# temp_module_v2_0_nov2023.net
KiCad netlist of a schematic drawn in EAGLE
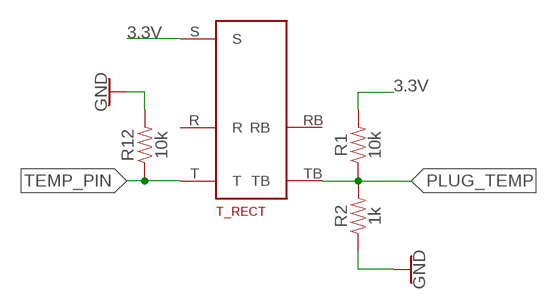
[diagram p0: schematic, sheet 1]
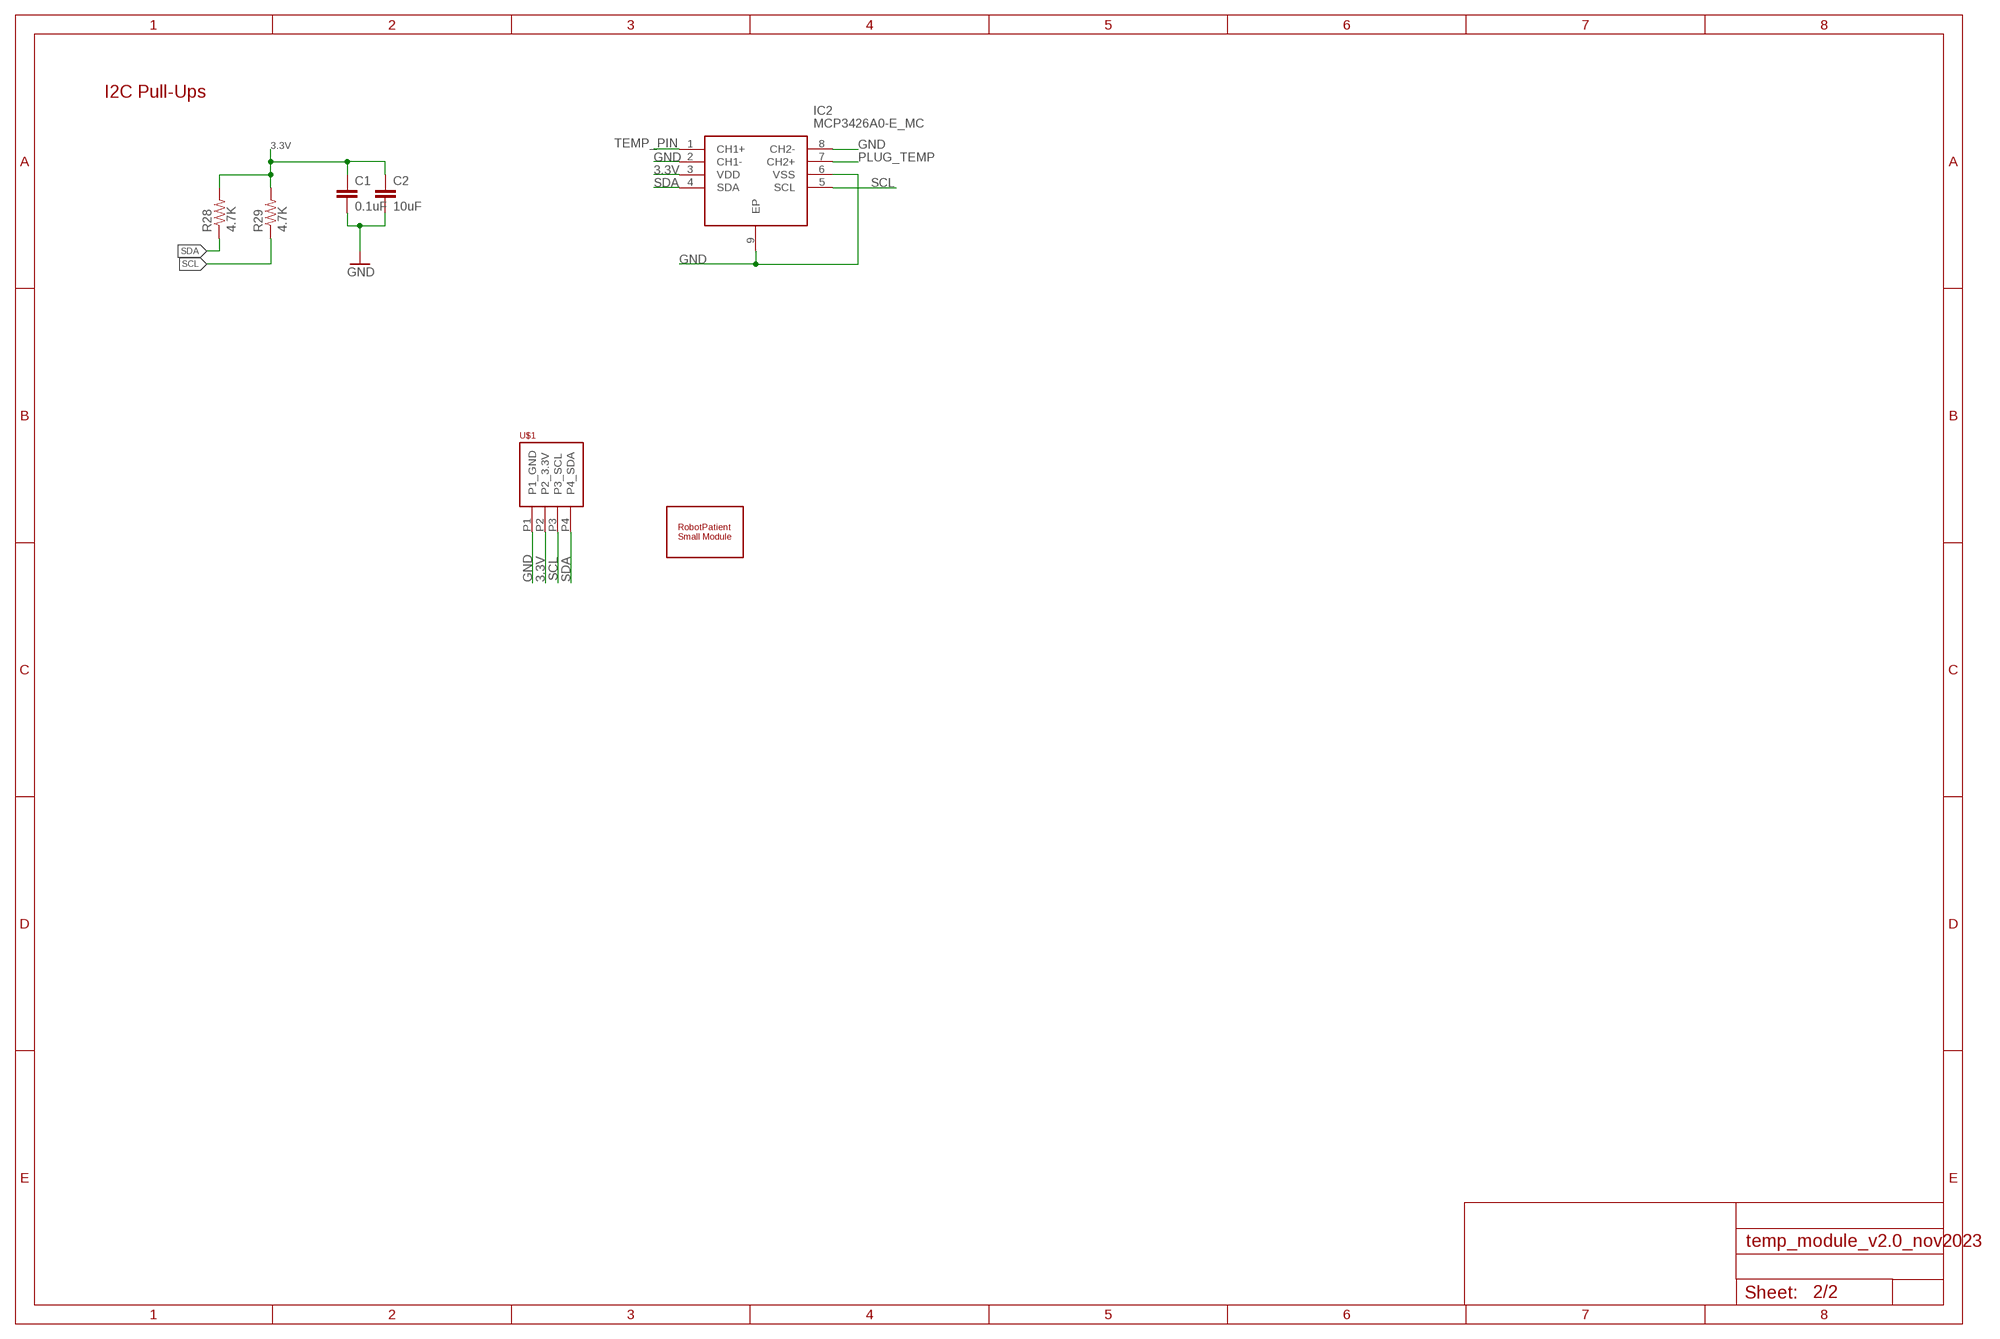
[diagram p1: schematic, sheet 2]

(export (version "E")
  (design (tool "Eeschema 10.0.6"))
  (components
    (comp (ref "C1")
      (value "0.1uF")
      (footprint "eagle-import:0603")
      (libsource (lib "eagle-import") (part "0.1UF-0603-25V-(+80/-20%)"))
    )
    (comp (ref "C2")
      (value "10uF")
      (footprint "eagle-import:0603")
      (libsource (lib "eagle-import") (part "10UF-0603-6.3V-20%"))
    )
    (comp (ref "IC2")
      (value "MCP3426A0-E_MC")
      (footprint "eagle-import:SON50P300X200X100-9N")
      (fields
        (field (name "MANUFACTURER_PART_NUMBER") "MCP3426A0-E/MC")
        (field (name "MOUSER_PART_NUMBER") "579-MCP3426A0E/MC")
      )
      (libsource (lib "eagle-import") (part "MCP3426A0-E_MC"))
    )
    (comp (ref "R28")
      (value "4.7K")
      (footprint "eagle-import:0603-RES")
      (libsource (lib "eagle-import") (part "4.7KOHM-1/10W-1%(0603)"))
    )
    (comp (ref "R29")
      (value "4.7K")
      (footprint "eagle-import:0603-RES")
      (libsource (lib "eagle-import") (part "4.7KOHM-1/10W-1%(0603)"))
    )
    (comp (ref "U$1")
      (value "PHOENIX_PTSM_M4_THANGLE")
      (footprint "eagle-import:PTSM_M4_TH")
      (libsource (lib "eagle-import") (part "PHOENIX_PTSM_M4_THANGLE"))
    )
    (comp (ref "U$2")
      (value "ROBOTPATIENT_SMALL_MODULEBOARD")
      (footprint "eagle-import:RP_SMALL_SENSOR_OUTLINE")
      (libsource (lib "eagle-import") (part "ROBOTPATIENT_SMALL_MODULEBOARD"))
    )
    (comp (ref "R1")
      (value "10k")
      (footprint "eagle-import:0603")
      (libsource (lib "eagle-import") (part "10KOHM-0603-1/10W-1%"))
    )
    (comp (ref "R2")
      (value "1k")
      (footprint "eagle-import:0603")
      (libsource (lib "eagle-import") (part "1KOHM-0603-1/10W-1%"))
    )
    (comp (ref "R12")
      (value "10k")
      (footprint "eagle-import:0603")
      (libsource (lib "eagle-import") (part "10KOHM-0603-1/10W-1%"))
    )
    (comp (ref "T_RECT")
      (value "SN37A1")
      (footprint "eagle-import:SN37A1")
      (libsource (lib "eagle-import") (part "SN37A1"))
    )
  )
  (nets
    (net (code "1") (name "3.3V") (class "Default")
      (node (ref "C1") (pin "1") (pinfunction "1_1") (pintype "passive"))
      (node (ref "C2") (pin "1") (pinfunction "1_1") (pintype "passive"))
      (node (ref "IC2") (pin "3") (pinfunction "VDD_3") (pintype "bidirectional"))
      (node (ref "R1") (pin "2") (pinfunction "2_2") (pintype "passive"))
      (node (ref "R28") (pin "2") (pinfunction "2_2") (pintype "passive"))
      (node (ref "R29") (pin "2") (pinfunction "2_2") (pintype "passive"))
      (node (ref "T_RECT") (pin "S") (pinfunction "S_S") (pintype "bidirectional"))
      (node (ref "U$1") (pin "P2") (pinfunction "P2_3.3V_P2") (pintype "power_in"))
    )
    (net (code "2") (name "GND") (class "Default")
      (node (ref "C1") (pin "2") (pinfunction "2_2") (pintype "passive"))
      (node (ref "C2") (pin "2") (pinfunction "2_2") (pintype "passive"))
      (node (ref "IC2") (pin "2") (pinfunction "CH1-_2") (pintype "bidirectional"))
      (node (ref "IC2") (pin "6") (pinfunction "VSS_6") (pintype "bidirectional"))
      (node (ref "IC2") (pin "8") (pinfunction "CH2-_8") (pintype "bidirectional"))
      (node (ref "IC2") (pin "9") (pinfunction "EP_9") (pintype "bidirectional"))
      (node (ref "R12") (pin "2") (pinfunction "2_2") (pintype "passive"))
      (node (ref "R2") (pin "1") (pinfunction "1_1") (pintype "passive"))
      (node (ref "U$1") (pin "P1") (pinfunction "P1_GND_P1") (pintype "power_in"))
    )
    (net (code "3") (name "PLUG_TEMP") (class "Default")
      (node (ref "IC2") (pin "7") (pinfunction "CH2+_7") (pintype "bidirectional"))
      (node (ref "R1") (pin "1") (pinfunction "1_1") (pintype "passive"))
      (node (ref "R2") (pin "2") (pinfunction "2_2") (pintype "passive"))
      (node (ref "T_RECT") (pin "TB") (pinfunction "TB_TB") (pintype "bidirectional"))
    )
    (net (code "4") (name "SCL") (class "Default")
      (node (ref "IC2") (pin "5") (pinfunction "SCL_5") (pintype "bidirectional"))
      (node (ref "R29") (pin "1") (pinfunction "1_1") (pintype "passive"))
      (node (ref "U$1") (pin "P3") (pinfunction "P3_SCL_P3") (pintype "bidirectional"))
    )
    (net (code "5") (name "SDA") (class "Default")
      (node (ref "IC2") (pin "4") (pinfunction "SDA_4") (pintype "bidirectional"))
      (node (ref "R28") (pin "1") (pinfunction "1_1") (pintype "passive"))
      (node (ref "U$1") (pin "P4") (pinfunction "P4_SDA_P4") (pintype "bidirectional"))
    )
    (net (code "6") (name "TEMP_PIN") (class "Default")
      (node (ref "IC2") (pin "1") (pinfunction "CH1+_1") (pintype "bidirectional"))
      (node (ref "R12") (pin "1") (pinfunction "1_1") (pintype "passive"))
      (node (ref "T_RECT") (pin "T") (pinfunction "T_T") (pintype "bidirectional"))
    )
    (net (code "7") (name "unconnected-(T_RECT-PadR)") (class "Default")
      (node (ref "T_RECT") (pin "R") (pinfunction "R_R") (pintype "bidirectional"))
    )
    (net (code "8") (name "unconnected-(T_RECT-PadRB)") (class "Default")
      (node (ref "T_RECT") (pin "RB") (pinfunction "RB_RB") (pintype "bidirectional"))
    )
  )
)
